# schematic_v1_0_4.net
KiCad netlist of a schematic drawn in EasyEDA
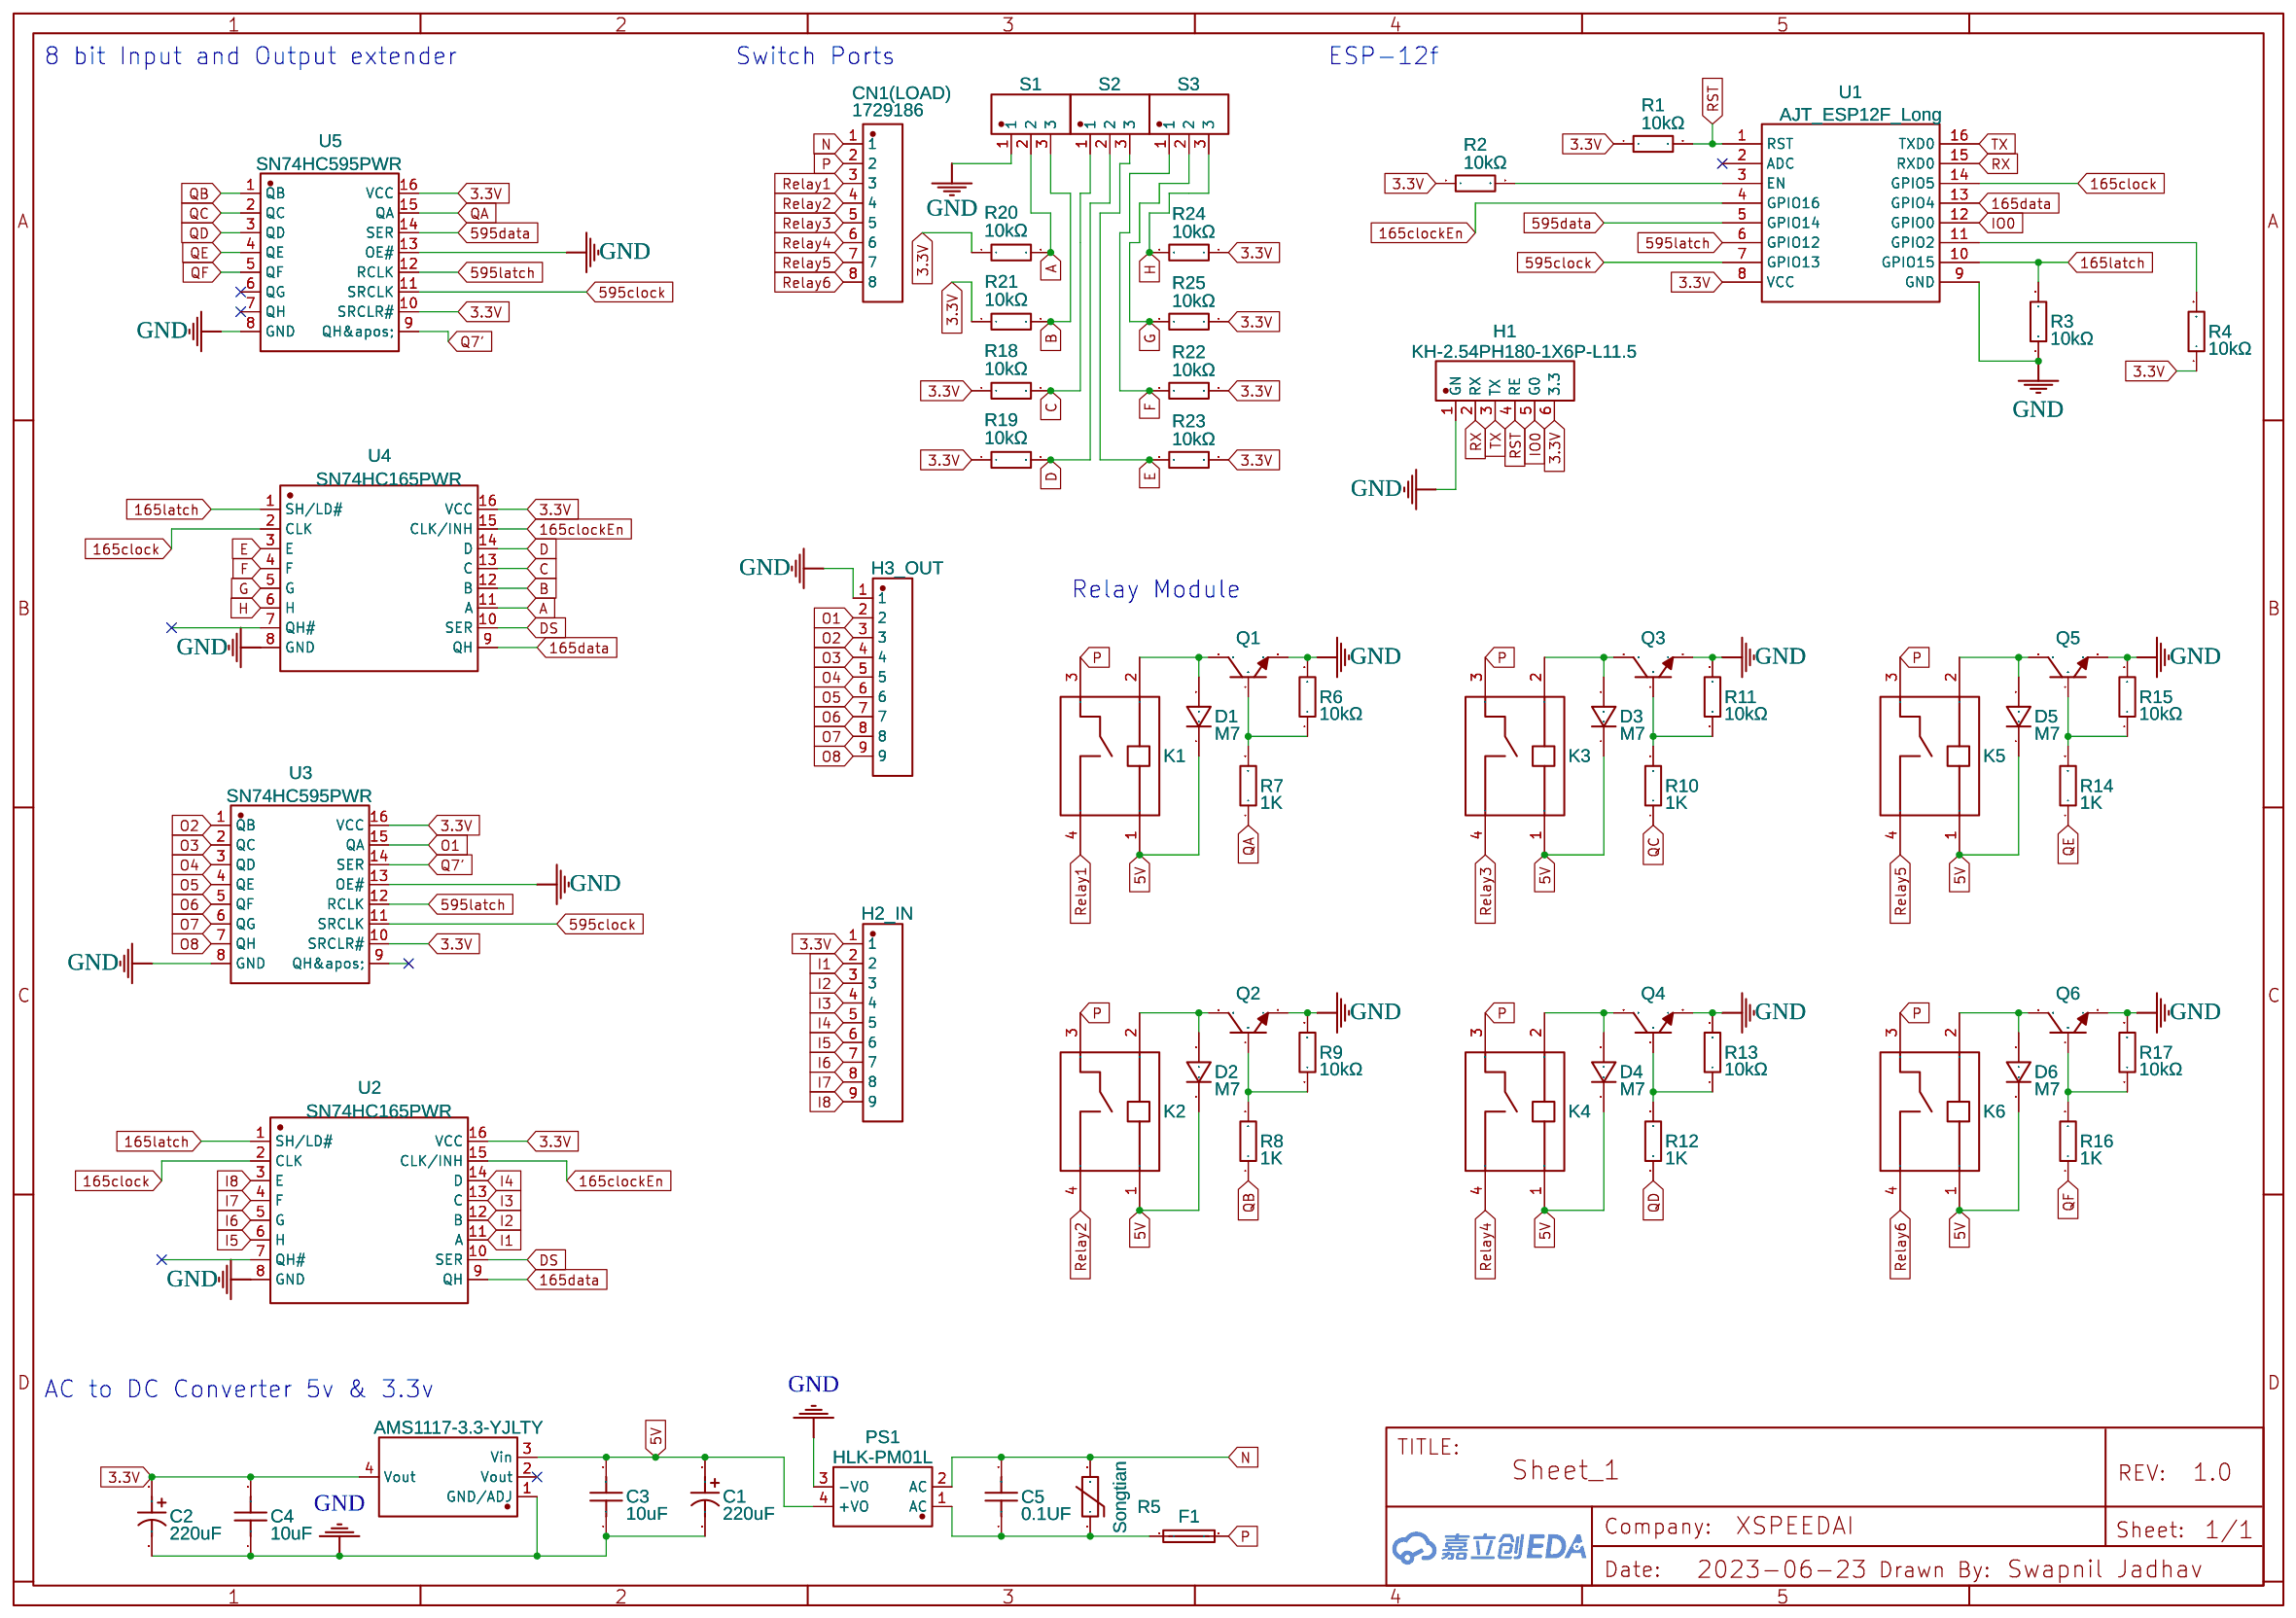
[diagram p0: schematic sheet]

(export (version "E")
  (design (tool "Eeschema 10.0.6"))
  (components
    (comp (ref "C1")
      (value "220uF")
      (fields
        (field (name "Manufacturer Part") "MVG 16V 220UF 6.3*7.7")
        (field (name "Manufacturer") "SAMYOUNG(韩国三莹)")
      )
      (libsource (lib "") (part "MVG 16V 220UF 6.3*7.7"))
    )
    (comp (ref "C2")
      (value "220uF")
      (fields
        (field (name "Manufacturer Part") "MVG 16V 220UF 6.3*7.7")
        (field (name "Manufacturer") "SAMYOUNG(韩国三莹)")
      )
      (libsource (lib "") (part "MVG 16V 220UF 6.3*7.7"))
    )
    (comp (ref "C3")
      (value "10uF")
      (fields
        (field (name "Manufacturer Part") "TCC0805X7R106K100FT")
        (field (name "Manufacturer") "CCTC(三环)")
      )
      (libsource (lib "") (part "TCC0805X7R106K100FT"))
    )
    (comp (ref "C4")
      (value "10uF")
      (fields
        (field (name "Manufacturer Part") "TCC0805X7R106K100FT")
        (field (name "Manufacturer") "CCTC(三环)")
      )
      (libsource (lib "") (part "TCC0805X7R106K100FT"))
    )
    (comp (ref "C5")
      (value "0.1UF")
      (fields
        (field (name "Manufacturer Part") "250V 0.1UF 5% CBBCapacitor")
        (field (name "Manufacturer") "ReliaPro")
      )
      (libsource (lib "") (part "250V 0.1UF 5% CBBCapacitor"))
    )
    (comp (ref "CN1(LOAD)")
      (value "1729186")
      (fields (field (name "Manufacturer") "Phoenix Contact(菲尼克斯)"))
      (libsource (lib "") (part "1729186"))
    )
    (comp (ref "D1")
      (value "M7")
      (fields (field (name "Manufacturer") "BORN(伯恩半导体)"))
      (libsource (lib "") (part "M7"))
    )
    (comp (ref "D2")
      (value "M7")
      (fields (field (name "Manufacturer") "BORN(伯恩半导体)"))
      (libsource (lib "") (part "M7"))
    )
    (comp (ref "D3")
      (value "M7")
      (fields (field (name "Manufacturer") "BORN(伯恩半导体)"))
      (libsource (lib "") (part "M7"))
    )
    (comp (ref "D4")
      (value "M7")
      (fields (field (name "Manufacturer") "BORN(伯恩半导体)"))
      (libsource (lib "") (part "M7"))
    )
    (comp (ref "D5")
      (value "M7")
      (fields (field (name "Manufacturer") "BORN(伯恩半导体)"))
      (libsource (lib "") (part "M7"))
    )
    (comp (ref "D6")
      (value "M7")
      (fields (field (name "Manufacturer") "BORN(伯恩半导体)"))
      (libsource (lib "") (part "M7"))
    )
    (comp (ref "F1")
      (value "2009T500MA250V")
      (fields (field (name "Manufacturer Part") "2009T500mA250V") (field (name "Manufacturer") "Hongda(泓达)"))
      (libsource (lib "") (part "2009T500MA250V"))
    )
    (comp (ref "H1")
      (value "KH-2.54PH180-1X6P-L11.5")
      (fields (field (name "Manufacturer") "kinghelm(金航标)"))
      (libsource (lib "") (part "KH-2.54PH180-1X6P-L11.5"))
    )
    (comp (ref "H2_IN")
      (value "KH-2.54PH180-1X9P-L11.5")
      (fields (field (name "Manufacturer") "kinghelm(金航标)"))
      (libsource (lib "") (part "KH-2.54PH180-1X9P-L11.5_1"))
    )
    (comp (ref "H3_OUT")
      (value "KH-2.54PH180-1X9P-L11.5")
      (fields (field (name "Manufacturer") "kinghelm(金航标)"))
      (libsource (lib "") (part "KH-2.54PH180-1X9P-L11.5"))
    )
    (comp (ref "K1")
      (value "HF7520-005-HSTP")
      (fields (field (name "Manufacturer") "HF(宏发)"))
      (libsource (lib "") (part "HF7520-005-HSTP"))
    )
    (comp (ref "K2")
      (value "HF7520-005-HSTP")
      (fields (field (name "Manufacturer") "HF(宏发)"))
      (libsource (lib "") (part "HF7520-005-HSTP"))
    )
    (comp (ref "K3")
      (value "HF7520-005-HSTP")
      (fields (field (name "Manufacturer") "HF(宏发)"))
      (libsource (lib "") (part "HF7520-005-HSTP"))
    )
    (comp (ref "K4")
      (value "HF7520-005-HSTP")
      (fields (field (name "Manufacturer") "HF(宏发)"))
      (libsource (lib "") (part "HF7520-005-HSTP"))
    )
    (comp (ref "K5")
      (value "HF7520-005-HSTP")
      (fields (field (name "Manufacturer") "HF(宏发)"))
      (libsource (lib "") (part "HF7520-005-HSTP"))
    )
    (comp (ref "K6")
      (value "HF7520-005-HSTP")
      (fields (field (name "Manufacturer") "HF(宏发)"))
      (libsource (lib "") (part "HF7520-005-HSTP"))
    )
    (comp (ref "NO1") (value "AMS1117-3.3-YJLTY") (libsource (lib "") (part "AMS1117-3.3-YJLTY")))
    (comp (ref "PS1")
      (value "HLK-PM01L")
      (fields (field (name "Manufacturer") "HI-LINK"))
      (libsource (lib "") (part "HLK-PM01L"))
    )
    (comp (ref "Q1")
      (value "SS8050_C181160")
      (fields (field (name "Manufacturer Part") "SS8050") (field (name "Manufacturer") "Hottech(合科泰)"))
      (libsource (lib "") (part "SS8050_C181160"))
    )
    (comp (ref "Q2")
      (value "SS8050_C181160")
      (fields (field (name "Manufacturer Part") "SS8050") (field (name "Manufacturer") "Hottech(合科泰)"))
      (libsource (lib "") (part "SS8050_C181160"))
    )
    (comp (ref "Q3")
      (value "SS8050_C181160")
      (fields (field (name "Manufacturer Part") "SS8050") (field (name "Manufacturer") "Hottech(合科泰)"))
      (libsource (lib "") (part "SS8050_C181160"))
    )
    (comp (ref "Q4")
      (value "SS8050_C181160")
      (fields (field (name "Manufacturer Part") "SS8050") (field (name "Manufacturer") "Hottech(合科泰)"))
      (libsource (lib "") (part "SS8050_C181160"))
    )
    (comp (ref "Q5")
      (value "SS8050_C181160")
      (fields (field (name "Manufacturer Part") "SS8050") (field (name "Manufacturer") "Hottech(合科泰)"))
      (libsource (lib "") (part "SS8050_C181160"))
    )
    (comp (ref "Q6")
      (value "SS8050_C181160")
      (fields (field (name "Manufacturer Part") "SS8050") (field (name "Manufacturer") "Hottech(合科泰)"))
      (libsource (lib "") (part "SS8050_C181160"))
    )
    (comp (ref "R1")
      (value "10kΩ")
      (fields
        (field (name "Manufacturer Part") "RMCF0805FT10K0")
        (field (name "Manufacturer") "SEI(Stackpole Electronics Inc.)")
      )
      (libsource (lib "") (part "RMCF0805FT10K0_1"))
    )
    (comp (ref "R2")
      (value "10kΩ")
      (fields
        (field (name "Manufacturer Part") "RMCF0805FT10K0")
        (field (name "Manufacturer") "SEI(Stackpole Electronics Inc.)")
      )
      (libsource (lib "") (part "RMCF0805FT10K0_1"))
    )
    (comp (ref "R3")
      (value "10kΩ")
      (fields
        (field (name "Manufacturer Part") "RMCF0805FT10K0")
        (field (name "Manufacturer") "SEI(Stackpole Electronics Inc.)")
      )
      (libsource (lib "") (part "RMCF0805FT10K0"))
    )
    (comp (ref "R4")
      (value "10kΩ")
      (fields
        (field (name "Manufacturer Part") "RMCF0805FT10K0")
        (field (name "Manufacturer") "SEI(Stackpole Electronics Inc.)")
      )
      (libsource (lib "") (part "RMCF0805FT10K0"))
    )
    (comp (ref "R5")
      (value "Songtian")
      (fields
        (field (name "Manufacturer Part") "STE10D431K1EQ0FST0R0")
        (field (name "Manufacturer") "STE(松田)")
      )
      (libsource (lib "") (part "STE10D431K1EQ0FST0R0"))
    )
    (comp (ref "R6")
      (value "10kΩ")
      (fields
        (field (name "Manufacturer Part") "RMCF0805FT10K0")
        (field (name "Manufacturer") "SEI(Stackpole Electronics Inc.)")
      )
      (libsource (lib "") (part "RMCF0805FT10K0"))
    )
    (comp (ref "R7")
      (value "1K")
      (fields (field (name "Manufacturer Part") "RT0805BRD071KL") (field (name "Manufacturer") "YAGEO(国巨)"))
      (libsource (lib "") (part "RT0805BRD071KL"))
    )
    (comp (ref "R8")
      (value "1K")
      (fields (field (name "Manufacturer Part") "RT0805BRD071KL") (field (name "Manufacturer") "YAGEO(国巨)"))
      (libsource (lib "") (part "RT0805BRD071KL"))
    )
    (comp (ref "R9")
      (value "10kΩ")
      (fields
        (field (name "Manufacturer Part") "RMCF0805FT10K0")
        (field (name "Manufacturer") "SEI(Stackpole Electronics Inc.)")
      )
      (libsource (lib "") (part "RMCF0805FT10K0"))
    )
    (comp (ref "R10")
      (value "1K")
      (fields (field (name "Manufacturer Part") "RT0805BRD071KL") (field (name "Manufacturer") "YAGEO(国巨)"))
      (libsource (lib "") (part "RT0805BRD071KL"))
    )
    (comp (ref "R11")
      (value "10kΩ")
      (fields
        (field (name "Manufacturer Part") "RMCF0805FT10K0")
        (field (name "Manufacturer") "SEI(Stackpole Electronics Inc.)")
      )
      (libsource (lib "") (part "RMCF0805FT10K0"))
    )
    (comp (ref "R12")
      (value "1K")
      (fields (field (name "Manufacturer Part") "RT0805BRD071KL") (field (name "Manufacturer") "YAGEO(国巨)"))
      (libsource (lib "") (part "RT0805BRD071KL"))
    )
    (comp (ref "R13")
      (value "10kΩ")
      (fields
        (field (name "Manufacturer Part") "RMCF0805FT10K0")
        (field (name "Manufacturer") "SEI(Stackpole Electronics Inc.)")
      )
      (libsource (lib "") (part "RMCF0805FT10K0"))
    )
    (comp (ref "R14")
      (value "1K")
      (fields (field (name "Manufacturer Part") "RT0805BRD071KL") (field (name "Manufacturer") "YAGEO(国巨)"))
      (libsource (lib "") (part "RT0805BRD071KL"))
    )
    (comp (ref "R15")
      (value "10kΩ")
      (fields
        (field (name "Manufacturer Part") "RMCF0805FT10K0")
        (field (name "Manufacturer") "SEI(Stackpole Electronics Inc.)")
      )
      (libsource (lib "") (part "RMCF0805FT10K0"))
    )
    (comp (ref "R16")
      (value "1K")
      (fields (field (name "Manufacturer Part") "RT0805BRD071KL") (field (name "Manufacturer") "YAGEO(国巨)"))
      (libsource (lib "") (part "RT0805BRD071KL"))
    )
    (comp (ref "R17")
      (value "10kΩ")
      (fields
        (field (name "Manufacturer Part") "RMCF0805FT10K0")
        (field (name "Manufacturer") "SEI(Stackpole Electronics Inc.)")
      )
      (libsource (lib "") (part "RMCF0805FT10K0"))
    )
    (comp (ref "R18")
      (value "10kΩ")
      (fields
        (field (name "Manufacturer Part") "RMCF0805FT10K0")
        (field (name "Manufacturer") "SEI(Stackpole Electronics Inc.)")
      )
      (libsource (lib "") (part "RMCF0805FT10K0_1"))
    )
    (comp (ref "R19")
      (value "10kΩ")
      (fields
        (field (name "Manufacturer Part") "RMCF0805FT10K0")
        (field (name "Manufacturer") "SEI(Stackpole Electronics Inc.)")
      )
      (libsource (lib "") (part "RMCF0805FT10K0_1"))
    )
    (comp (ref "R20")
      (value "10kΩ")
      (fields
        (field (name "Manufacturer Part") "RMCF0805FT10K0")
        (field (name "Manufacturer") "SEI(Stackpole Electronics Inc.)")
      )
      (libsource (lib "") (part "RMCF0805FT10K0_1"))
    )
    (comp (ref "R21")
      (value "10kΩ")
      (fields
        (field (name "Manufacturer Part") "RMCF0805FT10K0")
        (field (name "Manufacturer") "SEI(Stackpole Electronics Inc.)")
      )
      (libsource (lib "") (part "RMCF0805FT10K0_1"))
    )
    (comp (ref "R22")
      (value "10kΩ")
      (fields
        (field (name "Manufacturer Part") "RMCF0805FT10K0")
        (field (name "Manufacturer") "SEI(Stackpole Electronics Inc.)")
      )
      (libsource (lib "") (part "RMCF0805FT10K0_2"))
    )
    (comp (ref "R23")
      (value "10kΩ")
      (fields
        (field (name "Manufacturer Part") "RMCF0805FT10K0")
        (field (name "Manufacturer") "SEI(Stackpole Electronics Inc.)")
      )
      (libsource (lib "") (part "RMCF0805FT10K0_2"))
    )
    (comp (ref "R24")
      (value "10kΩ")
      (fields
        (field (name "Manufacturer Part") "RMCF0805FT10K0")
        (field (name "Manufacturer") "SEI(Stackpole Electronics Inc.)")
      )
      (libsource (lib "") (part "RMCF0805FT10K0_2"))
    )
    (comp (ref "R25")
      (value "10kΩ")
      (fields
        (field (name "Manufacturer Part") "RMCF0805FT10K0")
        (field (name "Manufacturer") "SEI(Stackpole Electronics Inc.)")
      )
      (libsource (lib "") (part "RMCF0805FT10K0_2"))
    )
    (comp (ref "S1")
      (value "TY381-3.5-03P-14-00AH")
      (fields (field (name "Manufacturer") "Toponelec(拓宜)"))
      (libsource (lib "") (part "TY381-3.5-03P-14-00AH"))
    )
    (comp (ref "S2")
      (value "TY381-3.5-03P-14-00AH")
      (fields (field (name "Manufacturer") "Toponelec(拓宜)"))
      (libsource (lib "") (part "TY381-3.5-03P-14-00AH"))
    )
    (comp (ref "S3")
      (value "TY381-3.5-03P-14-00AH")
      (fields (field (name "Manufacturer") "Toponelec(拓宜)"))
      (libsource (lib "") (part "TY381-3.5-03P-14-00AH"))
    )
    (comp (ref "U1") (value "AJT_ESP12F_Long") (libsource (lib "") (part "AJT_ESP12F_Long")))
    (comp (ref "U2")
      (value "SN74HC165PWR")
      (fields (field (name "Manufacturer") "TI(德州仪器)"))
      (libsource (lib "") (part "SN74HC165PWR"))
    )
    (comp (ref "U3")
      (value "SN74HC595PWR")
      (fields (field (name "Manufacturer") "TI(德州仪器)"))
      (libsource (lib "") (part "SN74HC595PWR"))
    )
    (comp (ref "U4")
      (value "SN74HC165PWR")
      (fields (field (name "Manufacturer") "TI(德州仪器)"))
      (libsource (lib "") (part "SN74HC165PWR"))
    )
    (comp (ref "U5")
      (value "SN74HC595PWR")
      (fields (field (name "Manufacturer") "TI(德州仪器)"))
      (libsource (lib "") (part "SN74HC595PWR"))
    )
  )
  (nets
    (net (code "1") (name "3.3V") (class "Default")
      (node (ref "C2") (pin "1") (pinfunction "1_1") (pintype "input"))
      (node (ref "C4") (pin "2") (pinfunction "2_2") (pintype "unspecified"))
      (node (ref "H1") (pin "6") (pinfunction "3.3_6") (pintype "unspecified"))
      (node (ref "H2_IN") (pin "1") (pinfunction "1_1") (pintype "unspecified"))
      (node (ref "NO1") (pin "4") (pinfunction "Vout_4") (pintype "unspecified"))
      (node (ref "R1") (pin "1") (pinfunction "1_1") (pintype "unspecified"))
      (node (ref "R18") (pin "1") (pinfunction "1_1") (pintype "unspecified"))
      (node (ref "R19") (pin "1") (pinfunction "1_1") (pintype "unspecified"))
      (node (ref "R2") (pin "1") (pinfunction "1_1") (pintype "unspecified"))
      (node (ref "R20") (pin "1") (pinfunction "1_1") (pintype "unspecified"))
      (node (ref "R21") (pin "1") (pinfunction "1_1") (pintype "unspecified"))
      (node (ref "R22") (pin "1") (pinfunction "1_1") (pintype "unspecified"))
      (node (ref "R23") (pin "1") (pinfunction "1_1") (pintype "unspecified"))
      (node (ref "R24") (pin "1") (pinfunction "1_1") (pintype "unspecified"))
      (node (ref "R25") (pin "1") (pinfunction "1_1") (pintype "unspecified"))
      (node (ref "R4") (pin "1") (pinfunction "1_1") (pintype "unspecified"))
      (node (ref "U1") (pin "8") (pinfunction "VCC_8") (pintype "unspecified"))
      (node (ref "U2") (pin "16") (pinfunction "VCC_16") (pintype "unspecified"))
      (node (ref "U3") (pin "10") (pinfunction "SRCLR#_10") (pintype "unspecified"))
      (node (ref "U3") (pin "16") (pinfunction "VCC_16") (pintype "unspecified"))
      (node (ref "U4") (pin "16") (pinfunction "VCC_16") (pintype "unspecified"))
      (node (ref "U5") (pin "10") (pinfunction "SRCLR#_10") (pintype "unspecified"))
      (node (ref "U5") (pin "16") (pinfunction "VCC_16") (pintype "unspecified"))
    )
    (net (code "2") (name "5V") (class "Default")
      (node (ref "C1") (pin "1") (pinfunction "1_1") (pintype "input"))
      (node (ref "C3") (pin "2") (pinfunction "2_2") (pintype "unspecified"))
      (node (ref "D1") (pin "1") (pinfunction "1_1") (pintype "unspecified"))
      (node (ref "D2") (pin "1") (pinfunction "1_1") (pintype "unspecified"))
      (node (ref "D3") (pin "1") (pinfunction "1_1") (pintype "unspecified"))
      (node (ref "D4") (pin "1") (pinfunction "1_1") (pintype "unspecified"))
      (node (ref "D5") (pin "1") (pinfunction "1_1") (pintype "unspecified"))
      (node (ref "D6") (pin "1") (pinfunction "1_1") (pintype "unspecified"))
      (node (ref "K1") (pin "1") (pinfunction "1_1") (pintype "unspecified"))
      (node (ref "K2") (pin "1") (pinfunction "1_1") (pintype "unspecified"))
      (node (ref "K3") (pin "1") (pinfunction "1_1") (pintype "unspecified"))
      (node (ref "K4") (pin "1") (pinfunction "1_1") (pintype "unspecified"))
      (node (ref "K5") (pin "1") (pinfunction "1_1") (pintype "unspecified"))
      (node (ref "K6") (pin "1") (pinfunction "1_1") (pintype "unspecified"))
      (node (ref "NO1") (pin "3") (pinfunction "Vin_3") (pintype "unspecified"))
      (node (ref "PS1") (pin "4") (pinfunction "+VO_4") (pintype "unspecified"))
    )
    (net (code "3") (name "165clock") (class "Default")
      (node (ref "U1") (pin "14") (pinfunction "GPIO5_14") (pintype "unspecified"))
      (node (ref "U2") (pin "2") (pinfunction "CLK_2") (pintype "unspecified"))
      (node (ref "U4") (pin "2") (pinfunction "CLK_2") (pintype "unspecified"))
    )
    (net (code "4") (name "165clockEn") (class "Default")
      (node (ref "U1") (pin "4") (pinfunction "GPIO16_4") (pintype "unspecified"))
      (node (ref "U2") (pin "15") (pinfunction "CLK/INH_15") (pintype "unspecified"))
      (node (ref "U4") (pin "15") (pinfunction "CLK/INH_15") (pintype "unspecified"))
    )
    (net (code "5") (name "165data") (class "Default")
      (node (ref "U1") (pin "13") (pinfunction "GPIO4_13") (pintype "unspecified"))
      (node (ref "U2") (pin "9") (pinfunction "QH_9") (pintype "unspecified"))
      (node (ref "U4") (pin "9") (pinfunction "QH_9") (pintype "unspecified"))
    )
    (net (code "6") (name "165latch") (class "Default")
      (node (ref "R3") (pin "2") (pinfunction "2_2") (pintype "unspecified"))
      (node (ref "U1") (pin "10") (pinfunction "GPIO15_10") (pintype "unspecified"))
      (node (ref "U2") (pin "1") (pinfunction "SH/LD#_1") (pintype "unspecified"))
      (node (ref "U4") (pin "1") (pinfunction "SH/LD#_1") (pintype "unspecified"))
    )
    (net (code "7") (name "595clock") (class "Default")
      (node (ref "U1") (pin "7") (pinfunction "GPIO13_7") (pintype "unspecified"))
      (node (ref "U3") (pin "11") (pinfunction "SRCLK_11") (pintype "unspecified"))
      (node (ref "U5") (pin "11") (pinfunction "SRCLK_11") (pintype "unspecified"))
    )
    (net (code "8") (name "595data") (class "Default")
      (node (ref "U1") (pin "5") (pinfunction "GPIO14_5") (pintype "unspecified"))
      (node (ref "U5") (pin "14") (pinfunction "SER_14") (pintype "unspecified"))
    )
    (net (code "9") (name "595latch") (class "Default")
      (node (ref "U1") (pin "6") (pinfunction "GPIO12_6") (pintype "unspecified"))
      (node (ref "U3") (pin "12") (pinfunction "RCLK_12") (pintype "unspecified"))
      (node (ref "U5") (pin "12") (pinfunction "RCLK_12") (pintype "unspecified"))
    )
    (net (code "10") (name "A") (class "Default")
      (node (ref "R20") (pin "2") (pinfunction "2_2") (pintype "unspecified"))
      (node (ref "S1") (pin "2") (pinfunction "2_2") (pintype "unspecified"))
      (node (ref "U4") (pin "11") (pinfunction "A_11") (pintype "unspecified"))
    )
    (net (code "11") (name "B") (class "Default")
      (node (ref "R21") (pin "2") (pinfunction "2_2") (pintype "unspecified"))
      (node (ref "S1") (pin "3") (pinfunction "3_3") (pintype "unspecified"))
      (node (ref "U4") (pin "12") (pinfunction "B_12") (pintype "unspecified"))
    )
    (net (code "12") (name "C") (class "Default")
      (node (ref "R18") (pin "2") (pinfunction "2_2") (pintype "unspecified"))
      (node (ref "S2") (pin "1") (pinfunction "1_1") (pintype "unspecified"))
      (node (ref "U4") (pin "13") (pinfunction "C_13") (pintype "unspecified"))
    )
    (net (code "13") (name "D") (class "Default")
      (node (ref "R19") (pin "2") (pinfunction "2_2") (pintype "unspecified"))
      (node (ref "S2") (pin "2") (pinfunction "2_2") (pintype "unspecified"))
      (node (ref "U4") (pin "14") (pinfunction "D_14") (pintype "unspecified"))
    )
    (net (code "14") (name "DS") (class "Default")
      (node (ref "U2") (pin "10") (pinfunction "SER_10") (pintype "unspecified"))
      (node (ref "U4") (pin "10") (pinfunction "SER_10") (pintype "unspecified"))
    )
    (net (code "15") (name "E") (class "Default")
      (node (ref "R23") (pin "2") (pinfunction "2_2") (pintype "unspecified"))
      (node (ref "S2") (pin "3") (pinfunction "3_3") (pintype "unspecified"))
      (node (ref "U4") (pin "3") (pinfunction "E_3") (pintype "unspecified"))
    )
    (net (code "16") (name "F") (class "Default")
      (node (ref "R22") (pin "2") (pinfunction "2_2") (pintype "unspecified"))
      (node (ref "S3") (pin "1") (pinfunction "1_1") (pintype "unspecified"))
      (node (ref "U4") (pin "4") (pinfunction "F_4") (pintype "unspecified"))
    )
    (net (code "17") (name "G") (class "Default")
      (node (ref "R25") (pin "2") (pinfunction "2_2") (pintype "unspecified"))
      (node (ref "S3") (pin "2") (pinfunction "2_2") (pintype "unspecified"))
      (node (ref "U4") (pin "5") (pinfunction "G_5") (pintype "unspecified"))
    )
    (net (code "18") (name "GND") (class "Default")
      (node (ref "C1") (pin "2") (pinfunction "2_2") (pintype "input"))
      (node (ref "C2") (pin "2") (pinfunction "2_2") (pintype "input"))
      (node (ref "C3") (pin "1") (pinfunction "1_1") (pintype "unspecified"))
      (node (ref "C4") (pin "1") (pinfunction "1_1") (pintype "unspecified"))
      (node (ref "H1") (pin "1") (pinfunction "GN_1") (pintype "unspecified"))
      (node (ref "H3_OUT") (pin "1") (pinfunction "1_1") (pintype "unspecified"))
      (node (ref "NO1") (pin "1") (pinfunction "GND/ADJ_1") (pintype "unspecified"))
      (node (ref "PS1") (pin "3") (pinfunction "-VO_3") (pintype "unspecified"))
      (node (ref "Q1") (pin "2") (pinfunction "E_2") (pintype "input"))
      (node (ref "Q2") (pin "2") (pinfunction "E_2") (pintype "input"))
      (node (ref "Q3") (pin "2") (pinfunction "E_2") (pintype "input"))
      (node (ref "Q4") (pin "2") (pinfunction "E_2") (pintype "input"))
      (node (ref "Q5") (pin "2") (pinfunction "E_2") (pintype "input"))
      (node (ref "Q6") (pin "2") (pinfunction "E_2") (pintype "input"))
      (node (ref "R11") (pin "2") (pinfunction "2_2") (pintype "unspecified"))
      (node (ref "R13") (pin "2") (pinfunction "2_2") (pintype "unspecified"))
      (node (ref "R15") (pin "2") (pinfunction "2_2") (pintype "unspecified"))
      (node (ref "R17") (pin "2") (pinfunction "2_2") (pintype "unspecified"))
      (node (ref "R3") (pin "1") (pinfunction "1_1") (pintype "unspecified"))
      (node (ref "R6") (pin "2") (pinfunction "2_2") (pintype "unspecified"))
      (node (ref "R9") (pin "2") (pinfunction "2_2") (pintype "unspecified"))
      (node (ref "S1") (pin "1") (pinfunction "1_1") (pintype "unspecified"))
      (node (ref "U1") (pin "9") (pinfunction "GND_9") (pintype "unspecified"))
      (node (ref "U2") (pin "8") (pinfunction "GND_8") (pintype "unspecified"))
      (node (ref "U3") (pin "13") (pinfunction "OE#_13") (pintype "unspecified"))
      (node (ref "U3") (pin "8") (pinfunction "GND_8") (pintype "unspecified"))
      (node (ref "U4") (pin "8") (pinfunction "GND_8") (pintype "unspecified"))
      (node (ref "U5") (pin "13") (pinfunction "OE#_13") (pintype "unspecified"))
      (node (ref "U5") (pin "8") (pinfunction "GND_8") (pintype "unspecified"))
    )
    (net (code "19") (name "H") (class "Default")
      (node (ref "R24") (pin "2") (pinfunction "2_2") (pintype "unspecified"))
      (node (ref "S3") (pin "3") (pinfunction "3_3") (pintype "unspecified"))
      (node (ref "U4") (pin "6") (pinfunction "H_6") (pintype "unspecified"))
    )
    (net (code "20") (name "I1") (class "Default")
      (node (ref "H2_IN") (pin "2") (pinfunction "2_2") (pintype "unspecified"))
      (node (ref "U2") (pin "11") (pinfunction "A_11") (pintype "unspecified"))
    )
    (net (code "21") (name "I2") (class "Default")
      (node (ref "H2_IN") (pin "3") (pinfunction "3_3") (pintype "unspecified"))
      (node (ref "U2") (pin "12") (pinfunction "B_12") (pintype "unspecified"))
    )
    (net (code "22") (name "I3") (class "Default")
      (node (ref "H2_IN") (pin "4") (pinfunction "4_4") (pintype "unspecified"))
      (node (ref "U2") (pin "13") (pinfunction "C_13") (pintype "unspecified"))
    )
    (net (code "23") (name "I4") (class "Default")
      (node (ref "H2_IN") (pin "5") (pinfunction "5_5") (pintype "unspecified"))
      (node (ref "U2") (pin "14") (pinfunction "D_14") (pintype "unspecified"))
    )
    (net (code "24") (name "I5") (class "Default")
      (node (ref "H2_IN") (pin "6") (pinfunction "6_6") (pintype "unspecified"))
      (node (ref "U2") (pin "6") (pinfunction "H_6") (pintype "unspecified"))
    )
    (net (code "25") (name "I6") (class "Default")
      (node (ref "H2_IN") (pin "7") (pinfunction "7_7") (pintype "unspecified"))
      (node (ref "U2") (pin "5") (pinfunction "G_5") (pintype "unspecified"))
    )
    (net (code "26") (name "I7") (class "Default")
      (node (ref "H2_IN") (pin "8") (pinfunction "8_8") (pintype "unspecified"))
      (node (ref "U2") (pin "4") (pinfunction "F_4") (pintype "unspecified"))
    )
    (net (code "27") (name "I8") (class "Default")
      (node (ref "H2_IN") (pin "9") (pinfunction "9_9") (pintype "unspecified"))
      (node (ref "U2") (pin "3") (pinfunction "E_3") (pintype "unspecified"))
    )
    (net (code "28") (name "IO0") (class "Default")
      (node (ref "H1") (pin "5") (pinfunction "G0_5") (pintype "unspecified"))
      (node (ref "U1") (pin "12") (pinfunction "GPIO0_12") (pintype "unspecified"))
    )
    (net (code "29") (name "N") (class "Default")
      (node (ref "C5") (pin "2") (pinfunction "2_2") (pintype "unspecified"))
      (node (ref "CN1(LOAD)") (pin "1") (pinfunction "1_1") (pintype "unspecified"))
      (node (ref "PS1") (pin "2") (pinfunction "AC_2") (pintype "unspecified"))
      (node (ref "R5") (pin "2") (pinfunction "2_2") (pintype "unspecified"))
    )
    (net (code "30") (name "Net-(C5-Pad1)") (class "Default")
      (node (ref "C5") (pin "1") (pinfunction "1_1") (pintype "unspecified"))
      (node (ref "F1") (pin "1") (pinfunction "1_1") (pintype "unspecified"))
      (node (ref "PS1") (pin "1") (pinfunction "AC_1") (pintype "unspecified"))
      (node (ref "R5") (pin "1") (pinfunction "1_1") (pintype "unspecified"))
    )
    (net (code "31") (name "Net-(Q1-B)") (class "Default")
      (node (ref "Q1") (pin "1") (pinfunction "B_1") (pintype "input"))
      (node (ref "R6") (pin "1") (pinfunction "1_1") (pintype "unspecified"))
      (node (ref "R7") (pin "2") (pinfunction "2_2") (pintype "input"))
    )
    (net (code "32") (name "Net-(Q1-C)") (class "Default")
      (node (ref "D1") (pin "2") (pinfunction "2_2") (pintype "unspecified"))
      (node (ref "K1") (pin "2") (pinfunction "2_2") (pintype "unspecified"))
      (node (ref "Q1") (pin "3") (pinfunction "C_3") (pintype "input"))
    )
    (net (code "33") (name "Net-(Q2-B)") (class "Default")
      (node (ref "Q2") (pin "1") (pinfunction "B_1") (pintype "input"))
      (node (ref "R8") (pin "2") (pinfunction "2_2") (pintype "input"))
      (node (ref "R9") (pin "1") (pinfunction "1_1") (pintype "unspecified"))
    )
    (net (code "34") (name "Net-(Q2-C)") (class "Default")
      (node (ref "D2") (pin "2") (pinfunction "2_2") (pintype "unspecified"))
      (node (ref "K2") (pin "2") (pinfunction "2_2") (pintype "unspecified"))
      (node (ref "Q2") (pin "3") (pinfunction "C_3") (pintype "input"))
    )
    (net (code "35") (name "Net-(Q3-B)") (class "Default")
      (node (ref "Q3") (pin "1") (pinfunction "B_1") (pintype "input"))
      (node (ref "R10") (pin "2") (pinfunction "2_2") (pintype "input"))
      (node (ref "R11") (pin "1") (pinfunction "1_1") (pintype "unspecified"))
    )
    (net (code "36") (name "Net-(Q3-C)") (class "Default")
      (node (ref "D3") (pin "2") (pinfunction "2_2") (pintype "unspecified"))
      (node (ref "K3") (pin "2") (pinfunction "2_2") (pintype "unspecified"))
      (node (ref "Q3") (pin "3") (pinfunction "C_3") (pintype "input"))
    )
    (net (code "37") (name "Net-(Q4-B)") (class "Default")
      (node (ref "Q4") (pin "1") (pinfunction "B_1") (pintype "input"))
      (node (ref "R12") (pin "2") (pinfunction "2_2") (pintype "input"))
      (node (ref "R13") (pin "1") (pinfunction "1_1") (pintype "unspecified"))
    )
    (net (code "38") (name "Net-(Q4-C)") (class "Default")
      (node (ref "D4") (pin "2") (pinfunction "2_2") (pintype "unspecified"))
      (node (ref "K4") (pin "2") (pinfunction "2_2") (pintype "unspecified"))
      (node (ref "Q4") (pin "3") (pinfunction "C_3") (pintype "input"))
    )
    (net (code "39") (name "Net-(Q5-B)") (class "Default")
      (node (ref "Q5") (pin "1") (pinfunction "B_1") (pintype "input"))
      (node (ref "R14") (pin "2") (pinfunction "2_2") (pintype "input"))
      (node (ref "R15") (pin "1") (pinfunction "1_1") (pintype "unspecified"))
    )
    (net (code "40") (name "Net-(Q5-C)") (class "Default")
      (node (ref "D5") (pin "2") (pinfunction "2_2") (pintype "unspecified"))
      (node (ref "K5") (pin "2") (pinfunction "2_2") (pintype "unspecified"))
      (node (ref "Q5") (pin "3") (pinfunction "C_3") (pintype "input"))
    )
    (net (code "41") (name "Net-(Q6-B)") (class "Default")
      (node (ref "Q6") (pin "1") (pinfunction "B_1") (pintype "input"))
      (node (ref "R16") (pin "2") (pinfunction "2_2") (pintype "input"))
      (node (ref "R17") (pin "1") (pinfunction "1_1") (pintype "unspecified"))
    )
    (net (code "42") (name "Net-(Q6-C)") (class "Default")
      (node (ref "D6") (pin "2") (pinfunction "2_2") (pintype "unspecified"))
      (node (ref "K6") (pin "2") (pinfunction "2_2") (pintype "unspecified"))
      (node (ref "Q6") (pin "3") (pinfunction "C_3") (pintype "input"))
    )
    (net (code "43") (name "Net-(U1-EN)") (class "Default")
      (node (ref "R2") (pin "2") (pinfunction "2_2") (pintype "unspecified"))
      (node (ref "U1") (pin "3") (pinfunction "EN_3") (pintype "unspecified"))
    )
    (net (code "44") (name "Net-(U1-GPIO2)") (class "Default")
      (node (ref "R4") (pin "2") (pinfunction "2_2") (pintype "unspecified"))
      (node (ref "U1") (pin "11") (pinfunction "GPIO2_11") (pintype "unspecified"))
    )
    (net (code "45") (name "O1") (class "Default")
      (node (ref "H3_OUT") (pin "2") (pinfunction "2_2") (pintype "unspecified"))
      (node (ref "U3") (pin "15") (pinfunction "QA_15") (pintype "unspecified"))
    )
    (net (code "46") (name "O2") (class "Default")
      (node (ref "H3_OUT") (pin "3") (pinfunction "3_3") (pintype "unspecified"))
      (node (ref "U3") (pin "1") (pinfunction "QB_1") (pintype "unspecified"))
    )
    (net (code "47") (name "O3") (class "Default")
      (node (ref "H3_OUT") (pin "4") (pinfunction "4_4") (pintype "unspecified"))
      (node (ref "U3") (pin "2") (pinfunction "QC_2") (pintype "unspecified"))
    )
    (net (code "48") (name "O4") (class "Default")
      (node (ref "H3_OUT") (pin "5") (pinfunction "5_5") (pintype "unspecified"))
      (node (ref "U3") (pin "3") (pinfunction "QD_3") (pintype "unspecified"))
    )
    (net (code "49") (name "O5") (class "Default")
      (node (ref "H3_OUT") (pin "6") (pinfunction "6_6") (pintype "unspecified"))
      (node (ref "U3") (pin "4") (pinfunction "QE_4") (pintype "unspecified"))
    )
    (net (code "50") (name "O6") (class "Default")
      (node (ref "H3_OUT") (pin "7") (pinfunction "7_7") (pintype "unspecified"))
      (node (ref "U3") (pin "5") (pinfunction "QF_5") (pintype "unspecified"))
    )
    (net (code "51") (name "O7") (class "Default")
      (node (ref "H3_OUT") (pin "8") (pinfunction "8_8") (pintype "unspecified"))
      (node (ref "U3") (pin "6") (pinfunction "QG_6") (pintype "unspecified"))
    )
    (net (code "52") (name "O8") (class "Default")
      (node (ref "H3_OUT") (pin "9") (pinfunction "9_9") (pintype "unspecified"))
      (node (ref "U3") (pin "7") (pinfunction "QH_7") (pintype "unspecified"))
    )
    (net (code "53") (name "P") (class "Default")
      (node (ref "CN1(LOAD)") (pin "2") (pinfunction "2_2") (pintype "unspecified"))
      (node (ref "F1") (pin "2") (pinfunction "2_2") (pintype "unspecified"))
      (node (ref "K1") (pin "3") (pinfunction "3_3") (pintype "unspecified"))
      (node (ref "K2") (pin "3") (pinfunction "3_3") (pintype "unspecified"))
      (node (ref "K3") (pin "3") (pinfunction "3_3") (pintype "unspecified"))
      (node (ref "K4") (pin "3") (pinfunction "3_3") (pintype "unspecified"))
      (node (ref "K5") (pin "3") (pinfunction "3_3") (pintype "unspecified"))
      (node (ref "K6") (pin "3") (pinfunction "3_3") (pintype "unspecified"))
    )
    (net (code "54") (name "Q7'") (class "Default")
      (node (ref "U3") (pin "14") (pinfunction "SER_14") (pintype "unspecified"))
      (node (ref "U5") (pin "9") (pinfunction "QH&apos;_9") (pintype "unspecified"))
    )
    (net (code "55") (name "QA") (class "Default")
      (node (ref "R7") (pin "1") (pinfunction "1_1") (pintype "input"))
      (node (ref "U5") (pin "15") (pinfunction "QA_15") (pintype "unspecified"))
    )
    (net (code "56") (name "QB") (class "Default")
      (node (ref "R8") (pin "1") (pinfunction "1_1") (pintype "input"))
      (node (ref "U5") (pin "1") (pinfunction "QB_1") (pintype "unspecified"))
    )
    (net (code "57") (name "QC") (class "Default")
      (node (ref "R10") (pin "1") (pinfunction "1_1") (pintype "input"))
      (node (ref "U5") (pin "2") (pinfunction "QC_2") (pintype "unspecified"))
    )
    (net (code "58") (name "QD") (class "Default")
      (node (ref "R12") (pin "1") (pinfunction "1_1") (pintype "input"))
      (node (ref "U5") (pin "3") (pinfunction "QD_3") (pintype "unspecified"))
    )
    (net (code "59") (name "QE") (class "Default")
      (node (ref "R14") (pin "1") (pinfunction "1_1") (pintype "input"))
      (node (ref "U5") (pin "4") (pinfunction "QE_4") (pintype "unspecified"))
    )
    (net (code "60") (name "QF") (class "Default")
      (node (ref "R16") (pin "1") (pinfunction "1_1") (pintype "input"))
      (node (ref "U5") (pin "5") (pinfunction "QF_5") (pintype "unspecified"))
    )
    (net (code "61") (name "RST") (class "Default")
      (node (ref "H1") (pin "4") (pinfunction "RE_4") (pintype "unspecified"))
      (node (ref "R1") (pin "2") (pinfunction "2_2") (pintype "unspecified"))
      (node (ref "U1") (pin "1") (pinfunction "RST_1") (pintype "unspecified"))
    )
    (net (code "62") (name "RX") (class "Default")
      (node (ref "H1") (pin "2") (pinfunction "RX_2") (pintype "unspecified"))
      (node (ref "U1") (pin "15") (pinfunction "RXD0_15") (pintype "unspecified"))
    )
    (net (code "63") (name "Relay1") (class "Default")
      (node (ref "CN1(LOAD)") (pin "3") (pinfunction "3_3") (pintype "unspecified"))
      (node (ref "K1") (pin "4") (pinfunction "4_4") (pintype "unspecified"))
    )
    (net (code "64") (name "Relay2") (class "Default")
      (node (ref "CN1(LOAD)") (pin "4") (pinfunction "4_4") (pintype "unspecified"))
      (node (ref "K2") (pin "4") (pinfunction "4_4") (pintype "unspecified"))
    )
    (net (code "65") (name "Relay3") (class "Default")
      (node (ref "CN1(LOAD)") (pin "5") (pinfunction "5_5") (pintype "unspecified"))
      (node (ref "K3") (pin "4") (pinfunction "4_4") (pintype "unspecified"))
    )
    (net (code "66") (name "Relay4") (class "Default")
      (node (ref "CN1(LOAD)") (pin "6") (pinfunction "6_6") (pintype "unspecified"))
      (node (ref "K4") (pin "4") (pinfunction "4_4") (pintype "unspecified"))
    )
    (net (code "67") (name "Relay5") (class "Default")
      (node (ref "CN1(LOAD)") (pin "7") (pinfunction "7_7") (pintype "unspecified"))
      (node (ref "K5") (pin "4") (pinfunction "4_4") (pintype "unspecified"))
    )
    (net (code "68") (name "Relay6") (class "Default")
      (node (ref "CN1(LOAD)") (pin "8") (pinfunction "8_8") (pintype "unspecified"))
      (node (ref "K6") (pin "4") (pinfunction "4_4") (pintype "unspecified"))
    )
    (net (code "69") (name "TX") (class "Default")
      (node (ref "H1") (pin "3") (pinfunction "TX_3") (pintype "unspecified"))
      (node (ref "U1") (pin "16") (pinfunction "TXD0_16") (pintype "unspecified"))
    )
    (net (code "70") (name "unconnected-(NO1-Vout-Pad2)") (class "Default")
      (node (ref "NO1") (pin "2") (pinfunction "Vout_2") (pintype "unspecified+no_connect"))
    )
    (net (code "71") (name "unconnected-(U1-ADC-Pad2)") (class "Default")
      (node (ref "U1") (pin "2") (pinfunction "ADC_2") (pintype "unspecified+no_connect"))
    )
    (net (code "72") (name "unconnected-(U2-QH#-Pad7)") (class "Default")
      (node (ref "U2") (pin "7") (pinfunction "QH#_7") (pintype "unspecified+no_connect"))
    )
    (net (code "73") (name "unconnected-(U3-QH&apos;-Pad9)") (class "Default")
      (node (ref "U3") (pin "9") (pinfunction "QH&apos;_9") (pintype "unspecified+no_connect"))
    )
    (net (code "74") (name "unconnected-(U4-QH#-Pad7)") (class "Default")
      (node (ref "U4") (pin "7") (pinfunction "QH#_7") (pintype "unspecified+no_connect"))
    )
    (net (code "75") (name "unconnected-(U5-QG-Pad6)") (class "Default")
      (node (ref "U5") (pin "6") (pinfunction "QG_6") (pintype "unspecified+no_connect"))
    )
    (net (code "76") (name "unconnected-(U5-QH-Pad7)") (class "Default")
      (node (ref "U5") (pin "7") (pinfunction "QH_7") (pintype "unspecified+no_connect"))
    )
  )
)
